# JacdacKeycapButtonBc30_135.net
KiCad netlist of a schematic drawn in Altium Designer
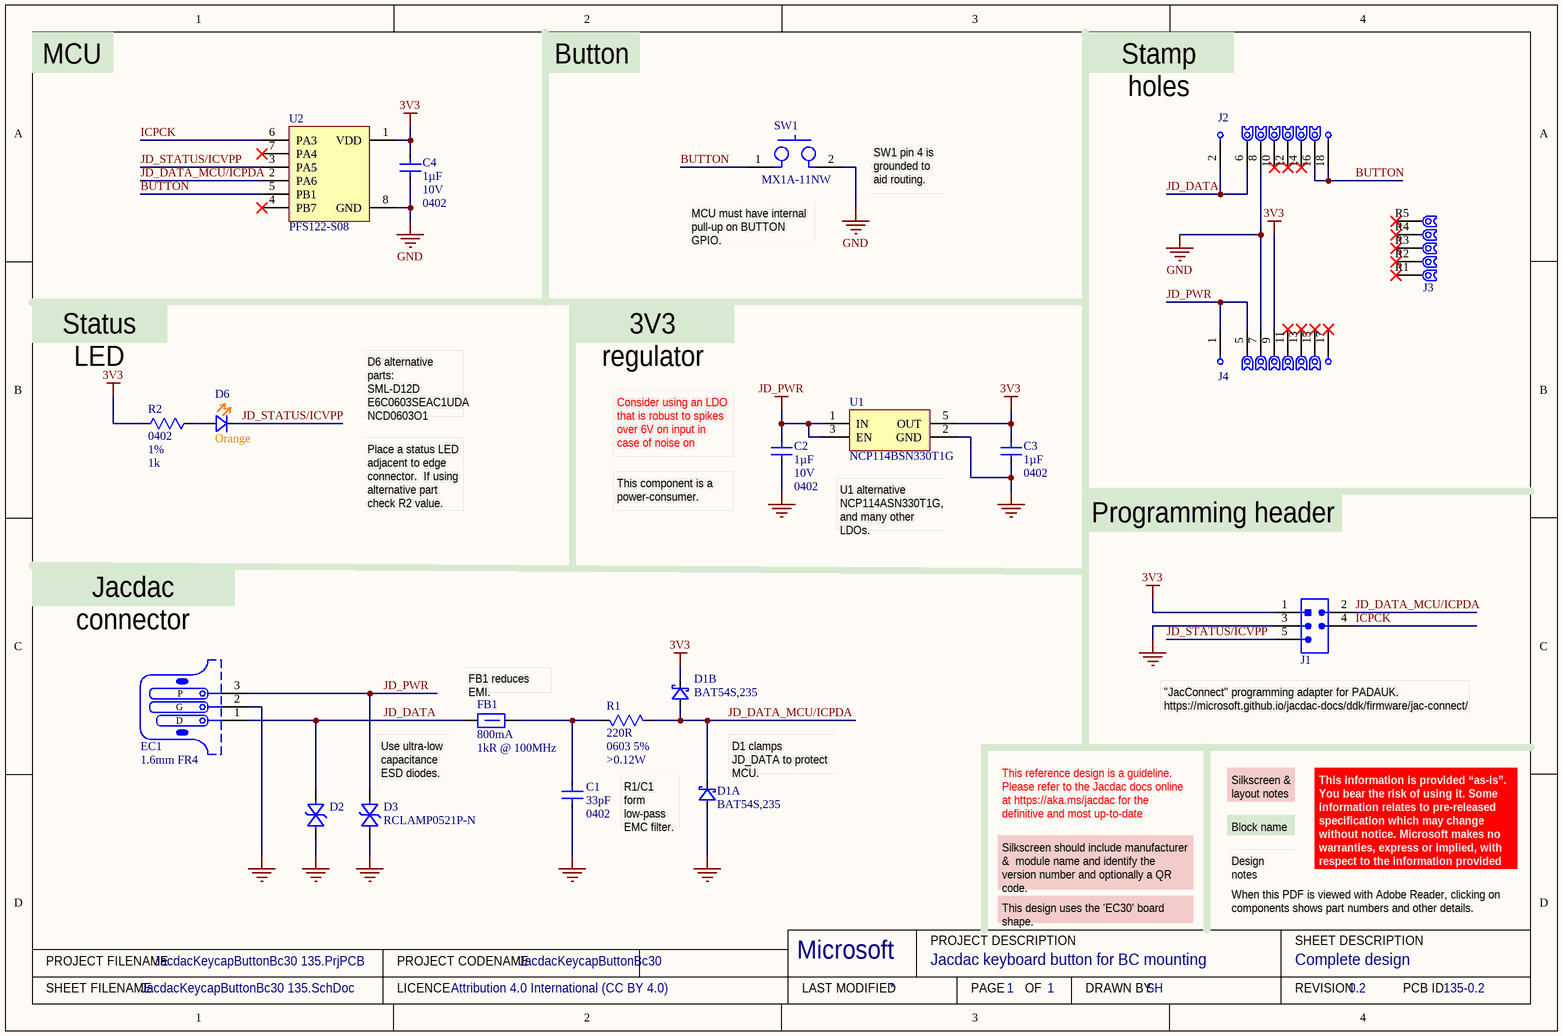
[diagram p0: JacdacKeycapButtonBc30 135.SchDoc]

(export (version "E")
  (design (tool "Eeschema 10.0.6"))
  (components
    (comp (ref "C1")
      (value "CL05C330JB5NNNC")
      (footprint "C0402_0.55MM - without outline")
      (description "CAP CER 33PF 50V C0G/NP0 0402")
      (fields
        (field (name "MANUFACTURER") "Samsung")
        (field (name "CASE CODE (IMPERIAL)") "0402")
        (field (name "TOLERANCE") "5%")
        (field (name "CAPACITANCE") "33pF")
      )
      (libsource (lib "Samsung") (part "CL05C330JB5NNNC"))
    )
    (comp (ref "C2")
      (value "CL05A105KP5NNNC")
      (footprint "C0402_0.55MM - without outline")
      (description "CAP CER 1UF 10V X5R 0402")
      (fields
        (field (name "MANUFACTURER") "Samsung")
        (field (name "TOLERANCE") "10%")
        (field (name "CAPACITANCE") "1µF")
        (field (name "VOLTAGE RATING") "10V")
        (field (name "CASE CODE (IMPERIAL)") "0402")
        (field (name "CREATED") "DG")
        (field (name "CHECKED") "?")
      )
      (libsource (lib "Samsung") (part "CL05A105KP5NNNC"))
    )
    (comp (ref "C3")
      (value "CL05A105KP5NNNC")
      (footprint "C0402_0.55MM - without outline")
      (description "CAP CER 1UF 10V X5R 0402")
      (fields
        (field (name "MANUFACTURER") "Samsung")
        (field (name "TOLERANCE") "10%")
        (field (name "CAPACITANCE") "1µF")
        (field (name "CASE CODE (IMPERIAL)") "0402")
        (field (name "CREATED") "DG")
        (field (name "CHECKED") "?")
      )
      (libsource (lib "Samsung") (part "CL05A105KP5NNNC"))
    )
    (comp (ref "C4")
      (value "CL05A105KP5NNNC")
      (footprint "C0402_0.55MM - without outline")
      (description "CAP CER 1UF 10V X5R 0402")
      (fields
        (field (name "MANUFACTURER") "Samsung")
        (field (name "TOLERANCE") "10%")
        (field (name "CAPACITANCE") "1µF")
        (field (name "VOLTAGE RATING") "10V")
        (field (name "CASE CODE (IMPERIAL)") "0402")
        (field (name "CREATED") "DG")
        (field (name "CHECKED") "?")
      )
      (libsource (lib "Samsung") (part "CL05A105KP5NNNC"))
    )
    (comp (ref "D1")
      (value "BAT54S")
      (footprint "NXP-BAT54S-TO-236AB - without outline")
      (description "DIODE ARRAY SCHOTTKY 30V SOT23")
      (fields (field (name "MANUFACTURER") "Nexperia") (field (name "MANUFACTURER PART NUMBER") "BAT54S,235"))
      (libsource (lib "NXP") (part "BAT54S"))
    )
    (comp (ref "D2")
      (value "RCLAMP0521P-N")
      (footprint "0402:TVS 0402 - XL")
      (description "Bidirectional 5V (Max) 6V 16V 3.5A (8/20us) 0402 TVS RoHS")
      (fields
        (field (name "MANUFACTURER") "Born Semiconductor")
        (field (name "CREATED BY") "D Gakure")
        (field (name "CHECKED BY") "?")
      )
      (libsource (lib "BornSemiconductor") (part "RCLAMP0521P-N"))
    )
    (comp (ref "D3")
      (value "RCLAMP0521P-N")
      (footprint "0402:TVS 0402 - XL")
      (description "Bidirectional 5V (Max) 6V 16V 3.5A (8/20us) 0402 TVS RoHS")
      (fields
        (field (name "MANUFACTURER") "Born Semiconductor")
        (field (name "MANUFACTURER PART NUMBER") "RCLAMP0521P-N")
        (field (name "CREATED BY") "D Gakure")
        (field (name "CHECKED BY") "?")
      )
      (libsource (lib "BornSemiconductor") (part "RCLAMP0521P-N"))
    )
    (comp (ref "D6")
      (value "~")
      (footprint "0603 Orange - without outline")
      (description "LED ORANGE DIFFUSED 1608 SMD")
      (fields
        (field (name "MANUFACTURER") "Everlight Elec")
        (field (name "MANUFACTURER PART NUMBER") "19-217/S2C-AQ1R1B/3T")
        (field (name "COLOUR") "Orange")
      )
      (libsource (lib "EverlightElec") (part "19-217/S2C-AQ1R1B/3T"))
    )
    (comp (ref "EC1")
      (value "3 pin JACDAC edge connector")
      (footprint "JACDAC_edge_connector:JACDAC_EDGE_CONNECTOR_NO_TRACES_3D_PADS")
      (description "3 pin Jacdac edge connector 1.27mm pitch")
      (fields
        (field (name "MANUFACTURER PART NUMBER") "JACDAC_EDGE_CONNECTOR")
        (field (name "PCB TYPE") "1.6mm FR4")
        (field (name "CHECKED BY") "?")
        (field (name "CREATED BY") "D. Gakure")
      )
      (libsource (lib "generic-con") (part "Jacdac edge connector"))
    )
    (comp (ref "FB1")
      (value "TDK MPZ1608S102ATA00")
      (footprint "TDK MPZ1608 0.8mm - without outline")
      (description "0603 1k@100MHz 0.8A chip")
      (fields
        (field (name "TOLERANCE") "25%")
        (field (name "MANUFACTURER") "TDK")
        (field (name "CURRENT RATING") "800mA")
        (field (name "IMPEDANCE") "1kR @ 100MHz")
      )
      (libsource (lib "TDK") (part "TDK MPZ1608S102ATA00"))
    )
    (comp (ref "J1")
      (value "Hack Connect Mini 1.27 mm pitch 2-row")
      (footprint "HackConnect:HACK_CONNECT_MINI_5_X_1_27_0.559mm_TH")
      (libsource (lib "generic-con") (part "HACK_CONNECT_MINI"))
    )
    (comp (ref "J2")
      (value "0.1\"")
      (footprint "generic-con-0.1inch:Jacdac BC30 stamp holes 20mm top x8")
      (description "2.54mm, 6/8 way")
      (fields (field (name "MANUFACTURER") "Generic") (field (name "MANUFACTURER PART NUMBER") "TBD"))
      (libsource (lib "generic-con") (part "Jacdac BC30 stamp holes 20mm top"))
    )
    (comp (ref "J3")
      (value "BC30 stamp holes")
      (footprint "generic-con-0.1inch:Jacdac BC30 stamp holes 10mm right x5")
      (description "2.54mm, 5 way")
      (fields (field (name "MANUFACTURER") "Generic") (field (name "MANUFACTURER PART NUMBER") "TBD"))
      (libsource (lib "generic-con") (part "Jacdac BC30 stamp holes 10mm right"))
    )
    (comp (ref "J4")
      (value "0.1\"")
      (footprint "generic-con-0.1inch:Jacdac BC30 stamp holes 20mm bottom x8")
      (description "2.54mm, 6/8 way")
      (fields (field (name "MANUFACTURER") "Generic") (field (name "MANUFACTURER PART NUMBER") "TBD"))
      (libsource (lib "generic-con") (part "Jacdac BC30 stamp holes 20mm bottom"))
    )
    (comp (ref "R1")
      (value "220R")
      (footprint "YAGEO-0603:RC0603")
      (description "Res Thick Film 0603 220 Ohm 1% 0.1W(1/10W) ±100ppm/°C Pad SMD T/R")
      (fields
        (field (name "TOLERANCE") "1%")
        (field (name "RESISTANCE") "220R")
        (field (name "CASE/PACKAGE") "0603")
        (field (name "COMMENT 1") "5%")
        (field (name "COMMENT 2") ">0.12W")
      )
      (libsource (lib "Yageo") (part "RC0603FR-07220RL"))
    )
    (comp (ref "R2")
      (value "RC0402FR-071KL")
      (footprint "R0402 - Without outline")
      (description "RES SMD 1K OHM 1% 1/16W 0402")
      (fields
        (field (name "MANUFACTURER") "Yageo")
        (field (name "CASE CODE (IMPERIAL)") "0402")
        (field (name "TOLERANCE") "1%")
        (field (name "RESISTANCE") "1k")
        (field (name "CREATED") "D.G")
        (field (name "CHECKED") "?")
      )
      (libsource (lib "Yageo") (part "RC0402FR-071KL"))
    )
    (comp (ref "SW1")
      (value "Mechanical keyboard mount")
      (footprint "MX1A-11NW:MX1A-11NW")
      (description "Pushbutton Switch SPST-NO Keyswitch Through Hole")
      (fields (field (name "MANUFACTURER PART NUMBER 1") "MX1A-11NW"))
      (libsource (lib "Cherry") (part "MX1A-11NW"))
    )
    (comp (ref "U1")
      (value "LDO 3.3V/300 mA")
      (footprint "ON_SEMI-SOT23-5 - without outline")
      (description "CMOS Low Dropout Regulator (LDO), 300 mA 3.3V, Non-Active Discharge, TSOP5")
      (fields
        (field (name "MANUFACTURER") "ON Semiconductor")
        (field (name "MANUFACTURER PART NUMBER") "NCP114BSN330T1G")
      )
      (libsource (lib "OnSemiconductor") (part "NCP114BSN330T1G"))
    )
    (comp (ref "U2")
      (value "PFS122-S08")
      (footprint "PADAUK-SOP-8:SOP-8")
      (description "8bit MTP MCU with 12-bit ADC")
      (fields (field (name "MANUFACTURER") "PADAUK") (field (name "MANUFACTURER PART NUMBER") "PFS122-S08"))
      (libsource (lib "PADAUK") (part "PFS122-SO8"))
    )
  )
  (nets
    (net (code "1") (name "/BUTTON") (class "Default")
      (node (ref "J2") (pin "16") (pinfunction "16_16") (pintype "passive"))
      (node (ref "J2") (pin "18") (pinfunction "18_18") (pintype "passive"))
      (node (ref "SW1") (pin "1") (pinfunction "A_1") (pintype "passive"))
      (node (ref "U2") (pin "5") (pinfunction "PB1_5") (pintype "passive"))
    )
    (net (code "2") (name "/ICPCK") (class "Default")
      (node (ref "J1") (pin "4") (pinfunction "SWCLK_4") (pintype "passive"))
      (node (ref "U2") (pin "6") (pinfunction "PA3_6") (pintype "passive"))
    )
    (net (code "3") (name "/JD_DATA") (class "Default")
      (node (ref "D2") (pin "1") (pinfunction "K_1") (pintype "passive"))
      (node (ref "EC1") (pin "1") (pinfunction "D_1") (pintype "passive"))
      (node (ref "FB1") (pin "1") (pinfunction "1_1") (pintype "passive"))
      (node (ref "J2") (pin "2") (pinfunction "2_2") (pintype "passive"))
      (node (ref "J2") (pin "6") (pinfunction "6_6") (pintype "passive"))
    )
    (net (code "4") (name "/JD_DATA_MCU{slash}ICPDA") (class "Default")
      (node (ref "D1") (pin "3") (pinfunction "K_3") (pintype "passive"))
      (node (ref "J1") (pin "2") (pinfunction "SWDIO_2") (pintype "passive"))
      (node (ref "R1") (pin "1") (pinfunction "1_1") (pintype "passive"))
      (node (ref "U2") (pin "2") (pinfunction "PA6_2") (pintype "passive"))
    )
    (net (code "5") (name "/JD_STATUS{slash}ICVPP") (class "Default")
      (node (ref "D6") (pin "1") (pinfunction "K_1") (pintype "passive"))
      (node (ref "J1") (pin "5") (pinfunction "RESET_5") (pintype "passive"))
      (node (ref "U2") (pin "3") (pinfunction "PA5_3") (pintype "passive"))
    )
    (net (code "6") (name "3V3") (class "Default")
      (node (ref "C3") (pin "2") (pinfunction "2_2") (pintype "passive"))
      (node (ref "C4") (pin "2") (pinfunction "2_2") (pintype "passive"))
      (node (ref "D1") (pin "2") (pinfunction "K_2") (pintype "passive"))
      (node (ref "J1") (pin "1") (pinfunction "VCC_1") (pintype "passive"))
      (node (ref "J4") (pin "9") (pinfunction "9_9") (pintype "passive"))
      (node (ref "R2") (pin "2") (pinfunction "2_2") (pintype "passive"))
      (node (ref "U1") (pin "5") (pinfunction "OUT_5") (pintype "passive"))
      (node (ref "U2") (pin "1") (pinfunction "VDD_1") (pintype "passive"))
    )
    (net (code "7") (name "GND") (class "Default")
      (node (ref "C1") (pin "1") (pinfunction "1_1") (pintype "passive"))
      (node (ref "C2") (pin "1") (pinfunction "1_1") (pintype "passive"))
      (node (ref "C3") (pin "1") (pinfunction "1_1") (pintype "passive"))
      (node (ref "C4") (pin "1") (pinfunction "1_1") (pintype "passive"))
      (node (ref "D1") (pin "1") (pinfunction "A_1") (pintype "passive"))
      (node (ref "D2") (pin "2") (pinfunction "A_2") (pintype "passive"))
      (node (ref "D3") (pin "2") (pinfunction "A_2") (pintype "passive"))
      (node (ref "EC1") (pin "2") (pinfunction "G_2") (pintype "passive"))
      (node (ref "J1") (pin "3") (pinfunction "GND_3") (pintype "passive"))
      (node (ref "J2") (pin "8") (pinfunction "8_8") (pintype "passive"))
      (node (ref "J4") (pin "7") (pinfunction "7_7") (pintype "passive"))
      (node (ref "SW1") (pin "2") (pinfunction "B_2") (pintype "passive"))
      (node (ref "U1") (pin "2") (pinfunction "GND_2") (pintype "passive"))
      (node (ref "U2") (pin "8") (pinfunction "GND_8") (pintype "passive"))
    )
    (net (code "8") (name "JD_PWR") (class "Default")
      (node (ref "C2") (pin "2") (pinfunction "2_2") (pintype "passive"))
      (node (ref "D3") (pin "1") (pinfunction "K_1") (pintype "passive"))
      (node (ref "EC1") (pin "3") (pinfunction "P_3") (pintype "passive"))
      (node (ref "J4") (pin "1") (pinfunction "1_1") (pintype "passive"))
      (node (ref "J4") (pin "5") (pinfunction "5_5") (pintype "passive"))
      (node (ref "U1") (pin "1") (pinfunction "IN_1") (pintype "passive"))
      (node (ref "U1") (pin "3") (pinfunction "EN_3") (pintype "passive"))
    )
    (net (code "9") (name "Net-(C1-Pad2)") (class "Default")
      (node (ref "C1") (pin "2") (pinfunction "2_2") (pintype "passive"))
      (node (ref "FB1") (pin "2") (pinfunction "2_2") (pintype "passive"))
      (node (ref "R1") (pin "2") (pinfunction "2_2") (pintype "passive"))
    )
    (net (code "10") (name "Net-(D6-A)") (class "Default")
      (node (ref "D6") (pin "2") (pinfunction "A_2") (pintype "passive"))
      (node (ref "R2") (pin "1") (pinfunction "1_1") (pintype "passive"))
    )
    (net (code "11") (name "unconnected-(J2-Pad10)") (class "Default")
      (node (ref "J2") (pin "10") (pinfunction "10_10") (pintype "passive+no_connect"))
    )
    (net (code "12") (name "unconnected-(J2-Pad12)") (class "Default")
      (node (ref "J2") (pin "12") (pinfunction "12_12") (pintype "passive+no_connect"))
    )
    (net (code "13") (name "unconnected-(J2-Pad14)") (class "Default")
      (node (ref "J2") (pin "14") (pinfunction "14_14") (pintype "passive+no_connect"))
    )
    (net (code "14") (name "unconnected-(J3-PadR1)") (class "Default")
      (node (ref "J3") (pin "R1") (pinfunction "R1_R1") (pintype "passive+no_connect"))
    )
    (net (code "15") (name "unconnected-(J3-PadR2)") (class "Default")
      (node (ref "J3") (pin "R2") (pinfunction "R2_R2") (pintype "passive+no_connect"))
    )
    (net (code "16") (name "unconnected-(J3-PadR3)") (class "Default")
      (node (ref "J3") (pin "R3") (pinfunction "R3_R3") (pintype "passive+no_connect"))
    )
    (net (code "17") (name "unconnected-(J3-PadR4)") (class "Default")
      (node (ref "J3") (pin "R4") (pinfunction "R4_R4") (pintype "passive+no_connect"))
    )
    (net (code "18") (name "unconnected-(J3-PadR5)") (class "Default")
      (node (ref "J3") (pin "R5") (pinfunction "R5_R5") (pintype "passive+no_connect"))
    )
    (net (code "19") (name "unconnected-(J4-Pad11)") (class "Default")
      (node (ref "J4") (pin "11") (pinfunction "11_11") (pintype "passive+no_connect"))
    )
    (net (code "20") (name "unconnected-(J4-Pad13)") (class "Default")
      (node (ref "J4") (pin "13") (pinfunction "13_13") (pintype "passive+no_connect"))
    )
    (net (code "21") (name "unconnected-(J4-Pad15)") (class "Default")
      (node (ref "J4") (pin "15") (pinfunction "15_15") (pintype "passive+no_connect"))
    )
    (net (code "22") (name "unconnected-(J4-Pad17)") (class "Default")
      (node (ref "J4") (pin "17") (pinfunction "17_17") (pintype "passive+no_connect"))
    )
    (net (code "23") (name "unconnected-(U2-PA4-Pad7)") (class "Default")
      (node (ref "U2") (pin "7") (pinfunction "PA4_7") (pintype "passive+no_connect"))
    )
    (net (code "24") (name "unconnected-(U2-PB7-Pad4)") (class "Default")
      (node (ref "U2") (pin "4") (pinfunction "PB7_4") (pintype "passive+no_connect"))
    )
  )
)
